# daisy.net
KiCad netlist of a schematic drawn in EAGLE
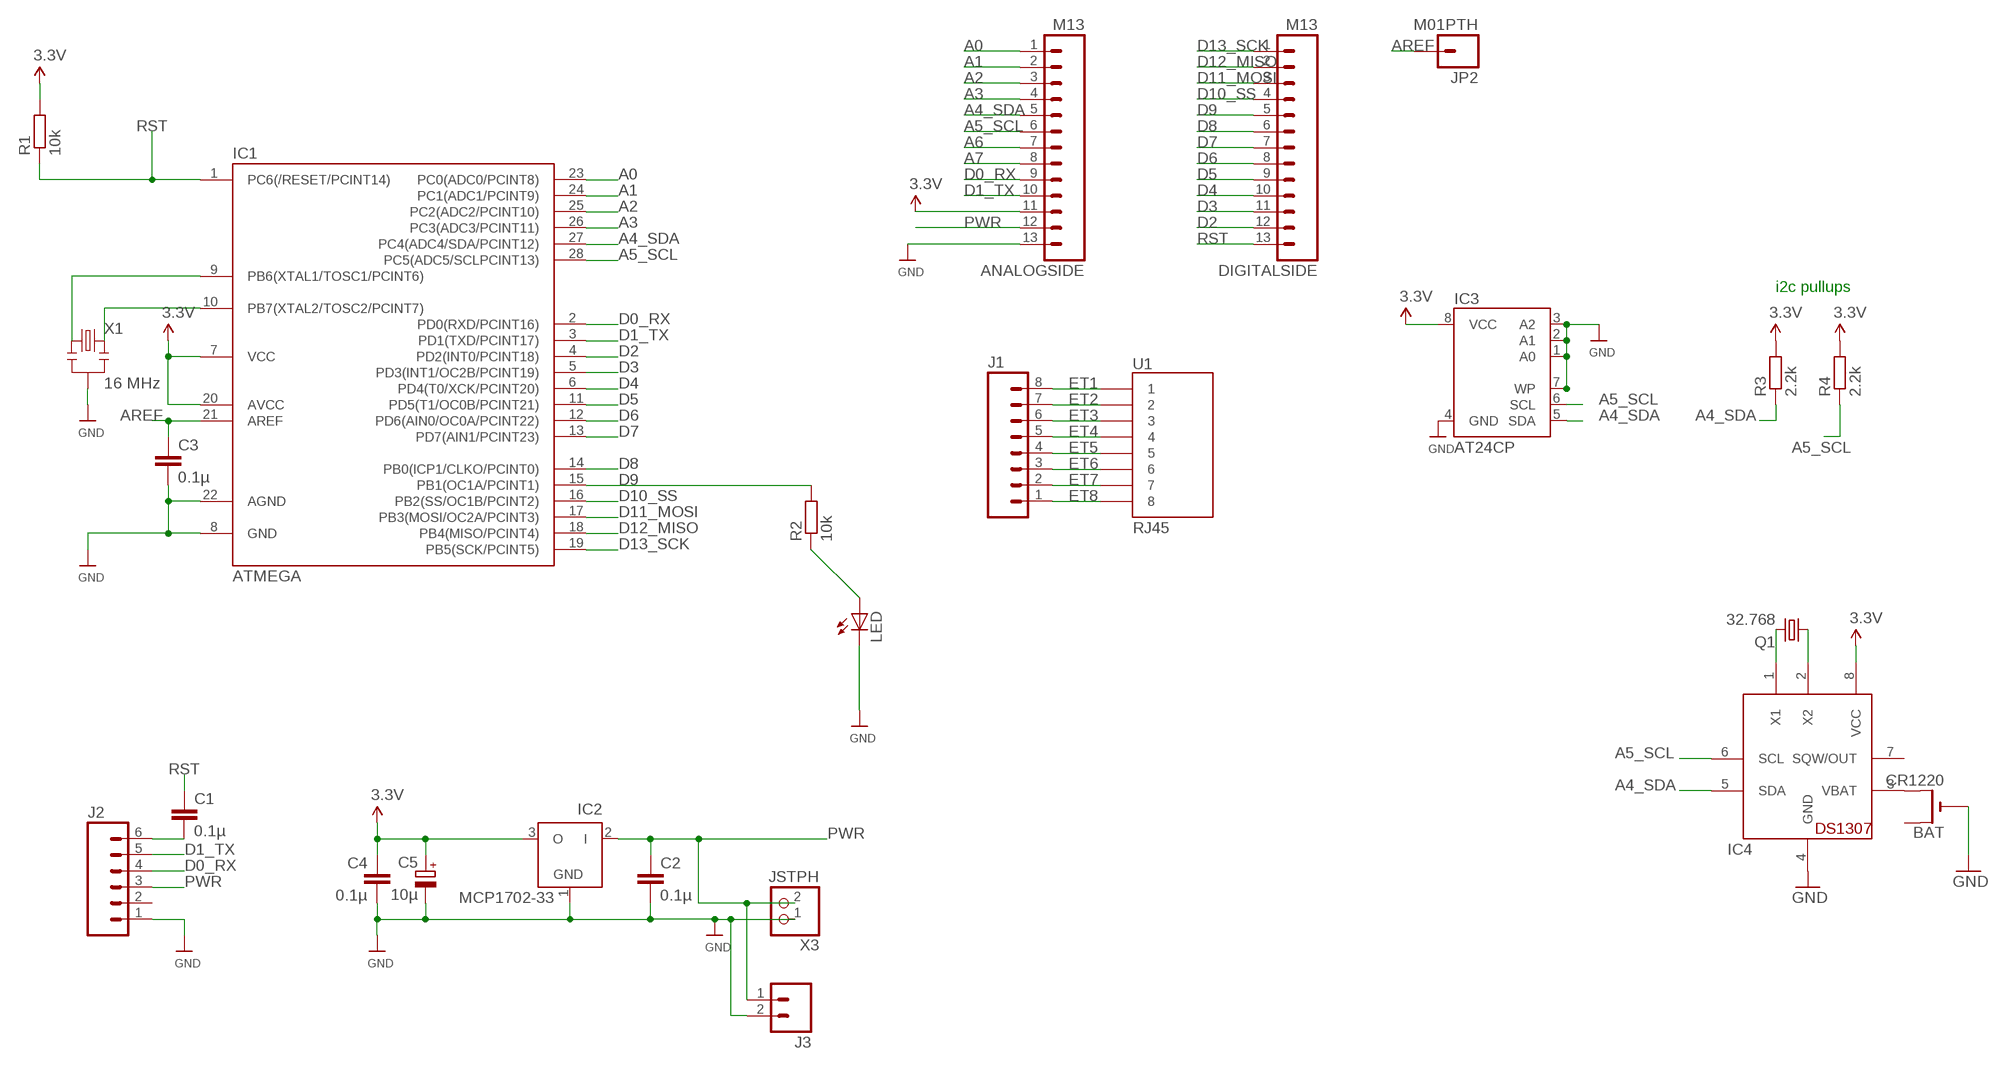
[diagram p0: schematic, sheet 1]

(export (version "E")
  (design (tool "Eeschema 10.0.6"))
  (components
    (comp (ref "ANALOGSIDE")
      (value "M13")
      (footprint "eagle-import:1X13")
      (libsource (lib "eagle-import") (part "M13"))
    )
    (comp (ref "BAT")
      (value "CR1220")
      (footprint "eagle-import:CR1220-THM")
      (libsource (lib "eagle-import") (part "CR1220THM"))
    )
    (comp (ref "C1")
      (value "0.1µ")
      (footprint "eagle-import:C025-024X044")
      (libsource (lib "eagle-import") (part "C-EU025-024X044"))
    )
    (comp (ref "C2")
      (value "0.1µ")
      (footprint "eagle-import:C025-024X044")
      (libsource (lib "eagle-import") (part "C-EU025-024X044"))
    )
    (comp (ref "C3")
      (value "0.1µ")
      (footprint "eagle-import:C025-024X044")
      (libsource (lib "eagle-import") (part "C-EU025-024X044"))
    )
    (comp (ref "C4")
      (value "0.1µ")
      (footprint "eagle-import:C025-024X044")
      (libsource (lib "eagle-import") (part "C-EU025-024X044"))
    )
    (comp (ref "C5")
      (value "10µ")
      (footprint "eagle-import:E1,8-4")
      (libsource (lib "eagle-import") (part "CPOL-EUE1.8-4"))
    )
    (comp (ref "DIGITALSIDE")
      (value "M13")
      (footprint "eagle-import:1X13")
      (libsource (lib "eagle-import") (part "M13"))
    )
    (comp (ref "IC1")
      (value "ATMEGA")
      (footprint "eagle-import:DIL28-3")
      (libsource (lib "eagle-import") (part "ATMEGA48/88/168-PU"))
    )
    (comp (ref "IC2")
      (value "MCP1702-33")
      (footprint "eagle-import:TO92")
      (libsource (lib "eagle-import") (part "MCP1702Z"))
    )
    (comp (ref "IC3")
      (value "AT24CP")
      (footprint "eagle-import:DIL08")
      (fields (field (name "MPN") "AT24C1024BW-SH-B"))
      (libsource (lib "eagle-import") (part "AT24CP"))
    )
    (comp (ref "IC4")
      (value "DS1307")
      (footprint "eagle-import:DIL08")
      (libsource (lib "eagle-import") (part "DS1307"))
    )
    (comp (ref "J1")
      (value "M08")
      (footprint "eagle-import:1X08_ROUND")
      (libsource (lib "eagle-import") (part "M08"))
    )
    (comp (ref "J2")
      (value "M06SILK_FEMALE_PTH")
      (footprint "eagle-import:1X06")
      (libsource (lib "eagle-import") (part "M06SILK_FEMALE_PTH"))
    )
    (comp (ref "J3")
      (value "M02PTH")
      (footprint "eagle-import:1X02")
      (libsource (lib "eagle-import") (part "M02PTH"))
    )
    (comp (ref "JP2")
      (value "M01PTH")
      (footprint "eagle-import:1X01")
      (libsource (lib "eagle-import") (part "M01PTH"))
    )
    (comp (ref "LED")
      (value "LED3MM")
      (footprint "eagle-import:LED3MM")
      (libsource (lib "eagle-import") (part "LED3MM"))
    )
    (comp (ref "Q1")
      (value "32.768")
      (footprint "eagle-import:TC38H")
      (libsource (lib "eagle-import") (part "CRYTALTC38H"))
    )
    (comp (ref "R1")
      (value "10k")
      (footprint "eagle-import:0204_7")
      (libsource (lib "eagle-import") (part "R-EU_0204/7"))
    )
    (comp (ref "R2")
      (value "10k")
      (footprint "eagle-import:0204_7")
      (libsource (lib "eagle-import") (part "R-EU_0204/7"))
    )
    (comp (ref "R3")
      (value "2.2k")
      (footprint "eagle-import:0204_7")
      (libsource (lib "eagle-import") (part "R-EU_0204/7"))
    )
    (comp (ref "R4")
      (value "2.2k")
      (footprint "eagle-import:0204_7")
      (libsource (lib "eagle-import") (part "R-EU_0204/7"))
    )
    (comp (ref "U1")
      (value "RJ45")
      (footprint "eagle-import:RJ45-8")
      (libsource (lib "eagle-import") (part "RJ45-8PTH"))
    )
    (comp (ref "X1")
      (value "16 MHz")
      (footprint "eagle-import:RESONATOR-PTH")
      (libsource (lib "eagle-import") (part "RESONATORPTH"))
    )
    (comp (ref "X3")
      (value "JSTPH")
      (footprint "eagle-import:JSTPH2")
      (libsource (lib "eagle-import") (part "CON_JST_PH_2PIN"))
    )
  )
  (nets
    (net (code "1") (name "/A0") (class "Default")
      (node (ref "ANALOGSIDE") (pin "1") (pinfunction "1_1") (pintype "passive"))
      (node (ref "IC1") (pin "23") (pinfunction "PC0(ADC0/PCINT8)_23") (pintype "bidirectional"))
    )
    (net (code "2") (name "/A1") (class "Default")
      (node (ref "ANALOGSIDE") (pin "2") (pinfunction "2_2") (pintype "passive"))
      (node (ref "IC1") (pin "24") (pinfunction "PC1(ADC1/PCINT9)_24") (pintype "bidirectional"))
    )
    (net (code "3") (name "/A2") (class "Default")
      (node (ref "ANALOGSIDE") (pin "3") (pinfunction "3_3") (pintype "passive"))
      (node (ref "IC1") (pin "25") (pinfunction "PC2(ADC2/PCINT10)_25") (pintype "bidirectional"))
    )
    (net (code "4") (name "/A3") (class "Default")
      (node (ref "ANALOGSIDE") (pin "4") (pinfunction "4_4") (pintype "passive"))
      (node (ref "IC1") (pin "26") (pinfunction "PC3(ADC3/PCINT11)_26") (pintype "bidirectional"))
    )
    (net (code "5") (name "/A4_SDA") (class "Default")
      (node (ref "ANALOGSIDE") (pin "5") (pinfunction "5_5") (pintype "passive"))
      (node (ref "IC1") (pin "27") (pinfunction "PC4(ADC4/SDA/PCINT12)_27") (pintype "bidirectional"))
      (node (ref "IC3") (pin "5") (pinfunction "SDA_5") (pintype "bidirectional"))
      (node (ref "IC4") (pin "5") (pinfunction "SDA_5") (pintype "bidirectional"))
      (node (ref "R3") (pin "1") (pinfunction "1_1") (pintype "passive"))
    )
    (net (code "6") (name "/A5_SCL") (class "Default")
      (node (ref "ANALOGSIDE") (pin "6") (pinfunction "6_6") (pintype "passive"))
      (node (ref "IC1") (pin "28") (pinfunction "PC5(ADC5/SCLPCINT13)_28") (pintype "bidirectional"))
      (node (ref "IC3") (pin "6") (pinfunction "SCL_6") (pintype "bidirectional"))
      (node (ref "IC4") (pin "6") (pinfunction "SCL_6") (pintype "bidirectional"))
      (node (ref "R4") (pin "1") (pinfunction "1_1") (pintype "passive"))
    )
    (net (code "7") (name "/A6") (class "Default")
      (node (ref "ANALOGSIDE") (pin "7") (pinfunction "7_7") (pintype "passive"))
    )
    (net (code "8") (name "/A7") (class "Default")
      (node (ref "ANALOGSIDE") (pin "8") (pinfunction "8_8") (pintype "passive"))
    )
    (net (code "9") (name "/AREF") (class "Default")
      (node (ref "C3") (pin "1") (pinfunction "1_1") (pintype "passive"))
      (node (ref "IC1") (pin "21") (pinfunction "AREF_21") (pintype "passive"))
      (node (ref "JP2") (pin "1") (pinfunction "1_1") (pintype "passive"))
    )
    (net (code "10") (name "/D0_RX") (class "Default")
      (node (ref "ANALOGSIDE") (pin "9") (pinfunction "9_9") (pintype "passive"))
      (node (ref "IC1") (pin "2") (pinfunction "PD0(RXD/PCINT16)_2") (pintype "bidirectional"))
      (node (ref "J2") (pin "4") (pinfunction "4_4") (pintype "passive"))
    )
    (net (code "11") (name "/D1_TX") (class "Default")
      (node (ref "ANALOGSIDE") (pin "10") (pinfunction "10_10") (pintype "passive"))
      (node (ref "IC1") (pin "3") (pinfunction "PD1(TXD/PCINT17)_3") (pintype "bidirectional"))
      (node (ref "J2") (pin "5") (pinfunction "5_5") (pintype "passive"))
    )
    (net (code "12") (name "/D2") (class "Default")
      (node (ref "DIGITALSIDE") (pin "12") (pinfunction "12_12") (pintype "passive"))
      (node (ref "IC1") (pin "4") (pinfunction "PD2(INT0/PCINT18)_4") (pintype "bidirectional"))
    )
    (net (code "13") (name "/D3") (class "Default")
      (node (ref "DIGITALSIDE") (pin "11") (pinfunction "11_11") (pintype "passive"))
      (node (ref "IC1") (pin "5") (pinfunction "PD3(INT1/OC2B/PCINT19)_5") (pintype "bidirectional"))
    )
    (net (code "14") (name "/D4") (class "Default")
      (node (ref "DIGITALSIDE") (pin "10") (pinfunction "10_10") (pintype "passive"))
      (node (ref "IC1") (pin "6") (pinfunction "PD4(T0/XCK/PCINT20)_6") (pintype "bidirectional"))
    )
    (net (code "15") (name "/D5") (class "Default")
      (node (ref "DIGITALSIDE") (pin "9") (pinfunction "9_9") (pintype "passive"))
      (node (ref "IC1") (pin "11") (pinfunction "PD5(T1/OC0B/PCINT21)_11") (pintype "bidirectional"))
    )
    (net (code "16") (name "/D6") (class "Default")
      (node (ref "DIGITALSIDE") (pin "8") (pinfunction "8_8") (pintype "passive"))
      (node (ref "IC1") (pin "12") (pinfunction "PD6(AIN0/OC0A/PCINT22)_12") (pintype "bidirectional"))
    )
    (net (code "17") (name "/D7") (class "Default")
      (node (ref "DIGITALSIDE") (pin "7") (pinfunction "7_7") (pintype "passive"))
      (node (ref "IC1") (pin "13") (pinfunction "PD7(AIN1/PCINT23)_13") (pintype "bidirectional"))
    )
    (net (code "18") (name "/D8") (class "Default")
      (node (ref "DIGITALSIDE") (pin "6") (pinfunction "6_6") (pintype "passive"))
      (node (ref "IC1") (pin "14") (pinfunction "PB0(ICP1/CLKO/PCINT0)_14") (pintype "bidirectional"))
    )
    (net (code "19") (name "/D9") (class "Default")
      (node (ref "DIGITALSIDE") (pin "5") (pinfunction "5_5") (pintype "passive"))
      (node (ref "IC1") (pin "15") (pinfunction "PB1(OC1A/PCINT1)_15") (pintype "bidirectional"))
      (node (ref "R2") (pin "2") (pinfunction "2_2") (pintype "passive"))
    )
    (net (code "20") (name "/D10_SS") (class "Default")
      (node (ref "DIGITALSIDE") (pin "4") (pinfunction "4_4") (pintype "passive"))
      (node (ref "IC1") (pin "16") (pinfunction "PB2(SS/OC1B/PCINT2)_16") (pintype "bidirectional"))
    )
    (net (code "21") (name "/D11_MOSI") (class "Default")
      (node (ref "DIGITALSIDE") (pin "3") (pinfunction "3_3") (pintype "passive"))
      (node (ref "IC1") (pin "17") (pinfunction "PB3(MOSI/OC2A/PCINT3)_17") (pintype "bidirectional"))
    )
    (net (code "22") (name "/D12_MISO") (class "Default")
      (node (ref "DIGITALSIDE") (pin "2") (pinfunction "2_2") (pintype "passive"))
      (node (ref "IC1") (pin "18") (pinfunction "PB4(MISO/PCINT4)_18") (pintype "bidirectional"))
    )
    (net (code "23") (name "/D13_SCK") (class "Default")
      (node (ref "DIGITALSIDE") (pin "1") (pinfunction "1_1") (pintype "passive"))
      (node (ref "IC1") (pin "19") (pinfunction "PB5(SCK/PCINT5)_19") (pintype "bidirectional"))
    )
    (net (code "24") (name "/ET1") (class "Default")
      (node (ref "J1") (pin "8") (pinfunction "8_8") (pintype "passive"))
      (node (ref "U1") (pin "1") (pinfunction "1_1") (pintype "bidirectional"))
    )
    (net (code "25") (name "/ET2") (class "Default")
      (node (ref "J1") (pin "7") (pinfunction "7_7") (pintype "passive"))
      (node (ref "U1") (pin "2") (pinfunction "2_2") (pintype "bidirectional"))
    )
    (net (code "26") (name "/ET3") (class "Default")
      (node (ref "J1") (pin "6") (pinfunction "6_6") (pintype "passive"))
      (node (ref "U1") (pin "3") (pinfunction "3_3") (pintype "bidirectional"))
    )
    (net (code "27") (name "/ET4") (class "Default")
      (node (ref "J1") (pin "5") (pinfunction "5_5") (pintype "passive"))
      (node (ref "U1") (pin "4") (pinfunction "4_4") (pintype "bidirectional"))
    )
    (net (code "28") (name "/ET5") (class "Default")
      (node (ref "J1") (pin "4") (pinfunction "4_4") (pintype "passive"))
      (node (ref "U1") (pin "5") (pinfunction "5_5") (pintype "bidirectional"))
    )
    (net (code "29") (name "/ET6") (class "Default")
      (node (ref "J1") (pin "3") (pinfunction "3_3") (pintype "passive"))
      (node (ref "U1") (pin "6") (pinfunction "6_6") (pintype "bidirectional"))
    )
    (net (code "30") (name "/ET7") (class "Default")
      (node (ref "J1") (pin "2") (pinfunction "2_2") (pintype "passive"))
      (node (ref "U1") (pin "7") (pinfunction "7_7") (pintype "bidirectional"))
    )
    (net (code "31") (name "/ET8") (class "Default")
      (node (ref "J1") (pin "1") (pinfunction "1_1") (pintype "passive"))
      (node (ref "U1") (pin "8") (pinfunction "8_8") (pintype "bidirectional"))
    )
    (net (code "32") (name "/PWR") (class "Default")
      (node (ref "ANALOGSIDE") (pin "12") (pinfunction "12_12") (pintype "passive"))
      (node (ref "C2") (pin "1") (pinfunction "1_1") (pintype "passive"))
      (node (ref "IC2") (pin "2") (pinfunction "I_2") (pintype "input"))
      (node (ref "J2") (pin "3") (pinfunction "3_3") (pintype "passive"))
      (node (ref "J3") (pin "1") (pinfunction "1_1") (pintype "passive"))
      (node (ref "X3") (pin "2") (pinfunction "2_2") (pintype "passive"))
    )
    (net (code "33") (name "/RST") (class "Default")
      (node (ref "C1") (pin "1") (pinfunction "1_1") (pintype "passive"))
      (node (ref "DIGITALSIDE") (pin "13") (pinfunction "13_13") (pintype "passive"))
      (node (ref "IC1") (pin "1") (pinfunction "PC6(/RESET/PCINT14)_1") (pintype "bidirectional"))
      (node (ref "R1") (pin "1") (pinfunction "1_1") (pintype "passive"))
    )
    (net (code "34") (name "3.3V") (class "Default")
      (node (ref "ANALOGSIDE") (pin "11") (pinfunction "11_11") (pintype "passive"))
      (node (ref "C4") (pin "1") (pinfunction "1_1") (pintype "passive"))
      (node (ref "C5") (pin "+") (pinfunction "+_+") (pintype "passive"))
      (node (ref "IC1") (pin "20") (pinfunction "AVCC_20") (pintype "passive"))
      (node (ref "IC1") (pin "7") (pinfunction "VCC_7") (pintype "power_in"))
      (node (ref "IC2") (pin "3") (pinfunction "O_3") (pintype "input"))
      (node (ref "IC3") (pin "8") (pinfunction "VCC_8") (pintype "power_in"))
      (node (ref "IC4") (pin "8") (pinfunction "VCC_8") (pintype "power_in"))
      (node (ref "R1") (pin "2") (pinfunction "2_2") (pintype "passive"))
      (node (ref "R3") (pin "2") (pinfunction "2_2") (pintype "passive"))
      (node (ref "R4") (pin "2") (pinfunction "2_2") (pintype "passive"))
    )
    (net (code "35") (name "GND") (class "Default")
      (node (ref "ANALOGSIDE") (pin "13") (pinfunction "13_13") (pintype "passive"))
      (node (ref "BAT") (pin "-") (pinfunction "-_-") (pintype "passive"))
      (node (ref "C2") (pin "2") (pinfunction "2_2") (pintype "passive"))
      (node (ref "C3") (pin "2") (pinfunction "2_2") (pintype "passive"))
      (node (ref "C4") (pin "2") (pinfunction "2_2") (pintype "passive"))
      (node (ref "C5") (pin "-") (pinfunction "-_-") (pintype "passive"))
      (node (ref "IC1") (pin "22") (pinfunction "AGND_22") (pintype "power_in"))
      (node (ref "IC1") (pin "8") (pinfunction "GND_8") (pintype "power_in"))
      (node (ref "IC2") (pin "1") (pinfunction "GND_1") (pintype "power_in"))
      (node (ref "IC3") (pin "1") (pinfunction "A0_1") (pintype "input"))
      (node (ref "IC3") (pin "2") (pinfunction "A1_2") (pintype "input"))
      (node (ref "IC3") (pin "3") (pinfunction "A2_3") (pintype "input"))
      (node (ref "IC3") (pin "4") (pinfunction "GND_4") (pintype "power_in"))
      (node (ref "IC3") (pin "7") (pinfunction "WP_7") (pintype "input"))
      (node (ref "IC4") (pin "4") (pinfunction "GND_4") (pintype "power_in"))
      (node (ref "J2") (pin "1") (pinfunction "1_1") (pintype "passive"))
      (node (ref "J3") (pin "2") (pinfunction "2_2") (pintype "passive"))
      (node (ref "LED") (pin "K") (pinfunction "C_K") (pintype "passive"))
      (node (ref "X1") (pin "2") (pinfunction "2_2") (pintype "passive"))
      (node (ref "X3") (pin "1") (pinfunction "1_1") (pintype "passive"))
    )
    (net (code "36") (name "Net-(BAT-+1)") (class "Default")
      (node (ref "BAT") (pin "+2") (pinfunction "+1_+2") (pintype "passive"))
      (node (ref "IC4") (pin "3") (pinfunction "VBAT_3") (pintype "power_in"))
    )
    (net (code "37") (name "Net-(C1-Pad2)") (class "Default")
      (node (ref "C1") (pin "2") (pinfunction "2_2") (pintype "passive"))
      (node (ref "J2") (pin "6") (pinfunction "6_6") (pintype "passive"))
    )
    (net (code "38") (name "Net-(IC1-PB6(XTAL1{slash}TOSC1{slash}PCINT6))") (class "Default")
      (node (ref "IC1") (pin "9") (pinfunction "PB6(XTAL1/TOSC1/PCINT6)_9") (pintype "bidirectional"))
      (node (ref "X1") (pin "1") (pinfunction "1_1") (pintype "passive"))
    )
    (net (code "39") (name "Net-(IC1-PB7(XTAL2{slash}TOSC2{slash}PCINT7))") (class "Default")
      (node (ref "IC1") (pin "10") (pinfunction "PB7(XTAL2/TOSC2/PCINT7)_10") (pintype "bidirectional"))
      (node (ref "X1") (pin "3") (pinfunction "3_3") (pintype "passive"))
    )
    (net (code "40") (name "Net-(IC4-X1)") (class "Default")
      (node (ref "IC4") (pin "1") (pinfunction "X1_1") (pintype "passive"))
      (node (ref "Q1") (pin "2") (pinfunction "2_2") (pintype "passive"))
    )
    (net (code "41") (name "Net-(IC4-X2)") (class "Default")
      (node (ref "IC4") (pin "2") (pinfunction "X2_2") (pintype "passive"))
      (node (ref "Q1") (pin "1") (pinfunction "1_1") (pintype "passive"))
    )
    (net (code "42") (name "Net-(LED-PadA)") (class "Default")
      (node (ref "LED") (pin "A") (pinfunction "A_A") (pintype "passive"))
      (node (ref "R2") (pin "1") (pinfunction "1_1") (pintype "passive"))
    )
    (net (code "43") (name "unconnected-(BAT-+-Pad+1)") (class "Default")
      (node (ref "BAT") (pin "+1") (pinfunction "+_+1") (pintype "passive"))
    )
    (net (code "44") (name "unconnected-(IC4-SQW{slash}OUT-Pad7)") (class "Default")
      (node (ref "IC4") (pin "7") (pinfunction "SQW/OUT_7") (pintype "bidirectional"))
    )
    (net (code "45") (name "unconnected-(J2-Pad2)") (class "Default")
      (node (ref "J2") (pin "2") (pinfunction "2_2") (pintype "passive"))
    )
  )
)
